# PCIE-to-USB3.net
KiCad netlist of a schematic drawn in Altium Designer
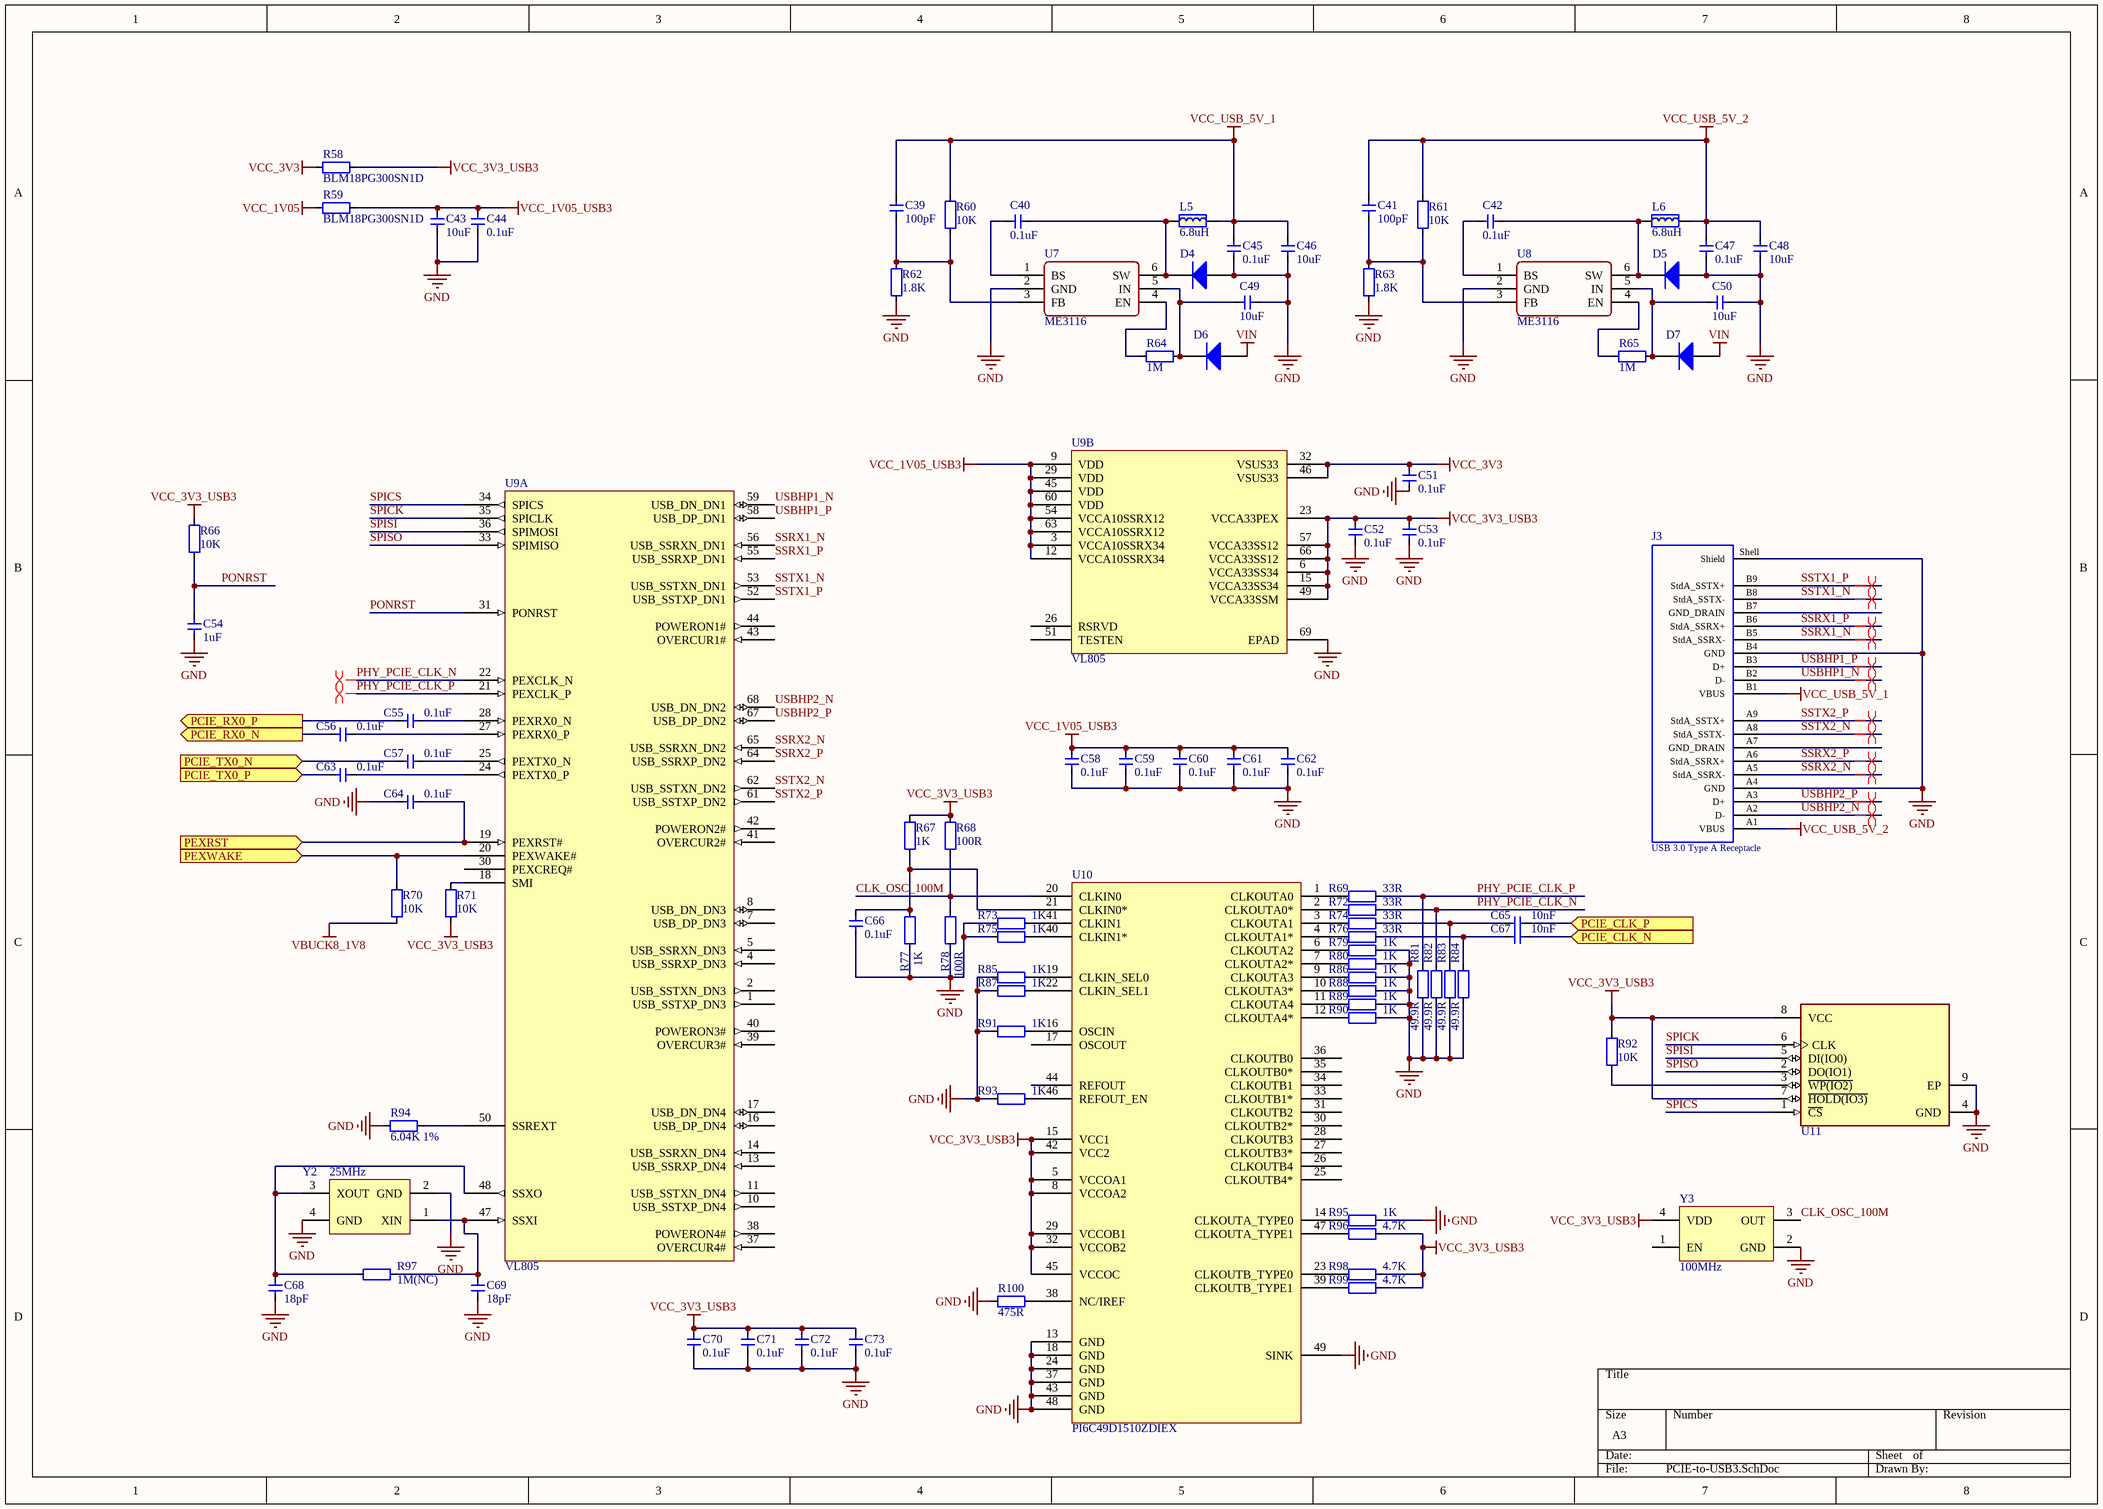
[diagram p0: PCIE-to-USB3.SchDoc]

(export (version "E")
  (design (tool "Eeschema 10.0.6"))
  (components
    (comp (ref "C39")
      (value "100pF")
      (footprint "CAP_0402")
      (description "Capacitor")
      (libsource (lib "MyPcbLib") (part "电容-0402"))
    )
    (comp (ref "C40")
      (value "0.1uF")
      (footprint "CAP_0402")
      (description "Capacitor")
      (libsource (lib "MyPcbLib") (part "电容-0402"))
    )
    (comp (ref "C41")
      (value "100pF")
      (footprint "CAP_0402")
      (description "Capacitor")
      (libsource (lib "MyPcbLib") (part "电容-0402"))
    )
    (comp (ref "C42")
      (value "0.1uF")
      (footprint "CAP_0402")
      (description "Capacitor")
      (libsource (lib "MyPcbLib") (part "电容-0402"))
    )
    (comp (ref "C43")
      (value "10uF")
      (footprint "CAP_0402")
      (description "Capacitor")
      (libsource (lib "MyPcbLib") (part "电容-0402"))
    )
    (comp (ref "C44")
      (value "0.1uF")
      (footprint "CAP_0402")
      (description "Capacitor")
      (libsource (lib "MyPcbLib") (part "电容-0402"))
    )
    (comp (ref "C45")
      (value "0.1uF")
      (footprint "CAP_0402")
      (description "Capacitor")
      (libsource (lib "MyPcbLib") (part "电容-0402"))
    )
    (comp (ref "C46")
      (value "10uF")
      (footprint "CAP_0402")
      (description "Capacitor")
      (libsource (lib "MyPcbLib") (part "电容-0402"))
    )
    (comp (ref "C47")
      (value "0.1uF")
      (footprint "CAP_0402")
      (description "Capacitor")
      (libsource (lib "MyPcbLib") (part "电容-0402"))
    )
    (comp (ref "C48")
      (value "10uF")
      (footprint "CAP_0402")
      (description "Capacitor")
      (libsource (lib "MyPcbLib") (part "电容-0402"))
    )
    (comp (ref "C49")
      (value "10uF")
      (footprint "CAP_0402")
      (description "Capacitor")
      (libsource (lib "MyPcbLib") (part "电容-0402"))
    )
    (comp (ref "C50")
      (value "10uF")
      (footprint "CAP_0402")
      (description "Capacitor")
      (libsource (lib "MyPcbLib") (part "电容-0402"))
    )
    (comp (ref "C51")
      (value "0.1uF")
      (footprint "CAP_0402")
      (description "Capacitor")
      (libsource (lib "MyPcbLib") (part "电容-0402"))
    )
    (comp (ref "C52")
      (value "0.1uF")
      (footprint "CAP_0402")
      (description "Capacitor")
      (libsource (lib "MyPcbLib") (part "电容-0402"))
    )
    (comp (ref "C53")
      (value "0.1uF")
      (footprint "CAP_0402")
      (description "Capacitor")
      (libsource (lib "MyPcbLib") (part "电容-0402"))
    )
    (comp (ref "C54")
      (value "1uF")
      (footprint "CAP_0402")
      (description "Capacitor")
      (libsource (lib "MyPcbLib") (part "电容-0402"))
    )
    (comp (ref "C55")
      (value "0.1uF")
      (footprint "CAP_0402")
      (description "Capacitor")
      (libsource (lib "MyPcbLib") (part "电容-0402"))
    )
    (comp (ref "C56")
      (value "0.1uF")
      (footprint "CAP_0402")
      (description "Capacitor")
      (libsource (lib "MyPcbLib") (part "电容-0402"))
    )
    (comp (ref "C57")
      (value "0.1uF")
      (footprint "CAP_0402")
      (description "Capacitor")
      (libsource (lib "MyPcbLib") (part "电容-0402"))
    )
    (comp (ref "C58")
      (value "0.1uF")
      (footprint "CAP_0402")
      (description "Capacitor")
      (libsource (lib "MyPcbLib") (part "电容-0402"))
    )
    (comp (ref "C59")
      (value "0.1uF")
      (footprint "CAP_0402")
      (description "Capacitor")
      (libsource (lib "MyPcbLib") (part "电容-0402"))
    )
    (comp (ref "C60")
      (value "0.1uF")
      (footprint "CAP_0402")
      (description "Capacitor")
      (libsource (lib "MyPcbLib") (part "电容-0402"))
    )
    (comp (ref "C61")
      (value "0.1uF")
      (footprint "CAP_0402")
      (description "Capacitor")
      (libsource (lib "MyPcbLib") (part "电容-0402"))
    )
    (comp (ref "C62")
      (value "0.1uF")
      (footprint "CAP_0402")
      (description "Capacitor")
      (libsource (lib "MyPcbLib") (part "电容-0402"))
    )
    (comp (ref "C63")
      (value "0.1uF")
      (footprint "CAP_0402")
      (description "Capacitor")
      (libsource (lib "MyPcbLib") (part "电容-0402"))
    )
    (comp (ref "C64")
      (value "0.1uF")
      (footprint "CAP_0402")
      (description "Capacitor")
      (libsource (lib "MyPcbLib") (part "电容-0402"))
    )
    (comp (ref "C65")
      (value "10nF")
      (footprint "CAP_0402")
      (description "Capacitor")
      (libsource (lib "MyPcbLib") (part "电容-0402"))
    )
    (comp (ref "C66")
      (value "0.1uF")
      (footprint "CAP_0402")
      (description "Capacitor")
      (libsource (lib "MyPcbLib") (part "电容-0402"))
    )
    (comp (ref "C67")
      (value "10nF")
      (footprint "CAP_0402")
      (description "Capacitor")
      (libsource (lib "MyPcbLib") (part "电容-0402"))
    )
    (comp (ref "C68")
      (value "18pF")
      (footprint "CAP_0402")
      (description "Capacitor")
      (libsource (lib "MyPcbLib") (part "电容-0402"))
    )
    (comp (ref "C69")
      (value "18pF")
      (footprint "CAP_0402")
      (description "Capacitor")
      (libsource (lib "MyPcbLib") (part "电容-0402"))
    )
    (comp (ref "C70")
      (value "0.1uF")
      (footprint "CAP_0402")
      (description "Capacitor")
      (libsource (lib "MyPcbLib") (part "电容-0402"))
    )
    (comp (ref "C71")
      (value "0.1uF")
      (footprint "CAP_0402")
      (description "Capacitor")
      (libsource (lib "MyPcbLib") (part "电容-0402"))
    )
    (comp (ref "C72")
      (value "0.1uF")
      (footprint "CAP_0402")
      (description "Capacitor")
      (libsource (lib "MyPcbLib") (part "电容-0402"))
    )
    (comp (ref "C73")
      (value "0.1uF")
      (footprint "CAP_0402")
      (description "Capacitor")
      (libsource (lib "MyPcbLib") (part "电容-0402"))
    )
    (comp (ref "D4")
      (value "二极管-5B5817WS")
      (footprint "SOD-323")
      (description "40V")
      (libsource (lib "MyPcbLib") (part "二极管-5B5817WS"))
    )
    (comp (ref "D5")
      (value "二极管-5B5817WS")
      (footprint "SOD-323")
      (description "40V")
      (libsource (lib "MyPcbLib") (part "二极管-5B5817WS"))
    )
    (comp (ref "D6")
      (value "二极管-5B5817WS")
      (footprint "SOD-323")
      (description "40V")
      (libsource (lib "MyPcbLib") (part "二极管-5B5817WS"))
    )
    (comp (ref "D7")
      (value "二极管-5B5817WS")
      (footprint "SOD-323")
      (description "40V")
      (libsource (lib "MyPcbLib") (part "二极管-5B5817WS"))
    )
    (comp (ref "J3")
      (value "USB 3.0 Type A Receptacle")
      (footprint "692141030100")
      (description "USB 3.0 Type A, Receptacle, Horizontal, THR, Dual Stacked")
      (fields
        (field (name "MANUFACTURER") "Wurth Elektronik")
        (field (name "MANUFACTURER PART NUMBER") "692141030100")
      )
      (libsource (lib "o80400v243+Altium_WR-USB+(rev20c)") (part "692141030100"))
    )
    (comp (ref "L5") (value "6.8uH") (footprint "IND-201612") (libsource (lib "MyPcbLib") (part "电感-201612")))
    (comp (ref "L6") (value "6.8uH") (footprint "IND-201612") (libsource (lib "MyPcbLib") (part "电感-201612")))
    (comp (ref "R58")
      (value "BLM18PG300SN1D")
      (footprint "0603-RES")
      (description "Resistor")
      (libsource (lib "MyPcbLib") (part "电阻-0603"))
    )
    (comp (ref "R59")
      (value "BLM18PG300SN1D")
      (footprint "0603-RES")
      (description "Resistor")
      (libsource (lib "MyPcbLib") (part "电阻-0603"))
    )
    (comp (ref "R60")
      (value "10K")
      (footprint "RES_0402")
      (description "Resistor")
      (libsource (lib "MyPcbLib") (part "电阻-0402"))
    )
    (comp (ref "R61")
      (value "10K")
      (footprint "RES_0402")
      (description "Resistor")
      (libsource (lib "MyPcbLib") (part "电阻-0402"))
    )
    (comp (ref "R62")
      (value "1.8K")
      (footprint "RES_0402")
      (description "Resistor")
      (libsource (lib "MyPcbLib") (part "电阻-0402"))
    )
    (comp (ref "R63")
      (value "1.8K")
      (footprint "RES_0402")
      (description "Resistor")
      (libsource (lib "MyPcbLib") (part "电阻-0402"))
    )
    (comp (ref "R64")
      (value "1M")
      (footprint "RES_0402")
      (description "Resistor")
      (libsource (lib "") (part "电阻-0402_1"))
    )
    (comp (ref "R65")
      (value "1M")
      (footprint "RES_0402")
      (description "Resistor")
      (libsource (lib "") (part "电阻-0402_1"))
    )
    (comp (ref "R66")
      (value "10K")
      (footprint "RES_0402")
      (description "Resistor")
      (libsource (lib "MyPcbLib") (part "电阻-0402"))
    )
    (comp (ref "R67")
      (value "1K")
      (footprint "RES_0402")
      (description "Resistor")
      (libsource (lib "MyPcbLib") (part "电阻-0402"))
    )
    (comp (ref "R68")
      (value "100R")
      (footprint "RES_0402")
      (description "Resistor")
      (libsource (lib "MyPcbLib") (part "电阻-0402"))
    )
    (comp (ref "R69")
      (value "33R")
      (footprint "RES_0402")
      (description "Resistor")
      (libsource (lib "") (part "电阻-0402_1"))
    )
    (comp (ref "R70")
      (value "10K")
      (footprint "RES_0402")
      (description "Resistor")
      (libsource (lib "MyPcbLib") (part "电阻-0402"))
    )
    (comp (ref "R71")
      (value "10K")
      (footprint "RES_0402")
      (description "Resistor")
      (libsource (lib "MyPcbLib") (part "电阻-0402"))
    )
    (comp (ref "R72")
      (value "33R")
      (footprint "RES_0402")
      (description "Resistor")
      (libsource (lib "") (part "电阻-0402_1"))
    )
    (comp (ref "R73")
      (value "1K")
      (footprint "RES_0402")
      (description "Resistor")
      (libsource (lib "") (part "电阻-0402_1"))
    )
    (comp (ref "R74")
      (value "33R")
      (footprint "RES_0402")
      (description "Resistor")
      (libsource (lib "") (part "电阻-0402_1"))
    )
    (comp (ref "R75")
      (value "1K")
      (footprint "RES_0402")
      (description "Resistor")
      (libsource (lib "") (part "电阻-0402_1"))
    )
    (comp (ref "R76")
      (value "33R")
      (footprint "RES_0402")
      (description "Resistor")
      (libsource (lib "") (part "电阻-0402_1"))
    )
    (comp (ref "R77")
      (value "1K")
      (footprint "RES_0402")
      (description "Resistor")
      (libsource (lib "MyPcbLib") (part "电阻-0402"))
    )
    (comp (ref "R78")
      (value "100R")
      (footprint "RES_0402")
      (description "Resistor")
      (libsource (lib "MyPcbLib") (part "电阻-0402"))
    )
    (comp (ref "R79")
      (value "1K")
      (footprint "RES_0402")
      (description "Resistor")
      (libsource (lib "") (part "电阻-0402_1"))
    )
    (comp (ref "R80")
      (value "1K")
      (footprint "RES_0402")
      (description "Resistor")
      (libsource (lib "") (part "电阻-0402_1"))
    )
    (comp (ref "R81")
      (value "49.9R")
      (footprint "RES_0402")
      (description "Resistor")
      (libsource (lib "") (part "电阻-0402_2"))
    )
    (comp (ref "R82")
      (value "49.9R")
      (footprint "RES_0402")
      (description "Resistor")
      (libsource (lib "") (part "电阻-0402_2"))
    )
    (comp (ref "R83")
      (value "49.9R")
      (footprint "RES_0402")
      (description "Resistor")
      (libsource (lib "") (part "电阻-0402_2"))
    )
    (comp (ref "R84")
      (value "49.9R")
      (footprint "RES_0402")
      (description "Resistor")
      (libsource (lib "") (part "电阻-0402_2"))
    )
    (comp (ref "R85")
      (value "1K")
      (footprint "RES_0402")
      (description "Resistor")
      (libsource (lib "") (part "电阻-0402_1"))
    )
    (comp (ref "R86")
      (value "1K")
      (footprint "RES_0402")
      (description "Resistor")
      (libsource (lib "") (part "电阻-0402_1"))
    )
    (comp (ref "R87")
      (value "1K")
      (footprint "RES_0402")
      (description "Resistor")
      (libsource (lib "") (part "电阻-0402_1"))
    )
    (comp (ref "R88")
      (value "1K")
      (footprint "RES_0402")
      (description "Resistor")
      (libsource (lib "") (part "电阻-0402_1"))
    )
    (comp (ref "R89")
      (value "1K")
      (footprint "RES_0402")
      (description "Resistor")
      (libsource (lib "") (part "电阻-0402_1"))
    )
    (comp (ref "R90")
      (value "1K")
      (footprint "RES_0402")
      (description "Resistor")
      (libsource (lib "") (part "电阻-0402_1"))
    )
    (comp (ref "R91")
      (value "1K")
      (footprint "RES_0402")
      (description "Resistor")
      (libsource (lib "") (part "电阻-0402_1"))
    )
    (comp (ref "R92")
      (value "10K")
      (footprint "RES_0402")
      (description "Resistor")
      (libsource (lib "") (part "电阻-0402_2"))
    )
    (comp (ref "R93")
      (value "1K")
      (footprint "RES_0402")
      (description "Resistor")
      (libsource (lib "") (part "电阻-0402_1"))
    )
    (comp (ref "R94")
      (value "6.04K 1%")
      (footprint "RES_0402")
      (description "Resistor")
      (libsource (lib "") (part "电阻-0402_3"))
    )
    (comp (ref "R95")
      (value "1K")
      (footprint "RES_0402")
      (description "Resistor")
      (libsource (lib "") (part "电阻-0402_1"))
    )
    (comp (ref "R96")
      (value "4.7K")
      (footprint "RES_0402")
      (description "Resistor")
      (libsource (lib "") (part "电阻-0402_1"))
    )
    (comp (ref "R97")
      (value "1M(NC)")
      (footprint "RES_0402")
      (description "Resistor")
      (libsource (lib "") (part "电阻-0402_1"))
    )
    (comp (ref "R98")
      (value "4.7K")
      (footprint "RES_0402")
      (description "Resistor")
      (libsource (lib "") (part "电阻-0402_1"))
    )
    (comp (ref "R99")
      (value "4.7K")
      (footprint "RES_0402")
      (description "Resistor")
      (libsource (lib "") (part "电阻-0402_1"))
    )
    (comp (ref "R100")
      (value "475R")
      (footprint "RES_0402")
      (description "Resistor")
      (libsource (lib "") (part "电阻-0402_3"))
    )
    (comp (ref "U7")
      (value "ME3116")
      (footprint "SOT23-6")
      (description "DC-DC")
      (libsource (lib "MyPcbLib") (part "ME3116"))
    )
    (comp (ref "U8")
      (value "ME3116")
      (footprint "SOT23-6")
      (description "DC-DC")
      (libsource (lib "MyPcbLib") (part "ME3116"))
    )
    (comp (ref "U9")
      (value "VL805")
      (footprint "QFN-68-0.4MM")
      (description "PCIE to USB3.0")
      (libsource (lib "mLib") (part "VL805"))
    )
    (comp (ref "U10")
      (value "PI6C49D1510ZDIEX")
      (footprint "QFN-48_7X7")
      (libsource (lib "MyPcbLib") (part "PI6C49D1510ZDIEX"))
    )
    (comp (ref "U11")
      (value "W25Q80DVUXIE_TR")
      (footprint "SPI-FLASH-USON")
      (libsource (lib "MyPcbLib") (part "W25Q80DVUXIE_TR"))
    )
    (comp (ref "Y2")
      (value "25MHz")
      (footprint "晶振2520")
      (description "2520无源")
      (fields (field (name "MF") "ECS International") (field (name "MP") "ECS-3225S30-240-EN-TR"))
      (libsource (lib "MyPcbLib") (part "晶振-4Pin-无源"))
    )
    (comp (ref "Y3")
      (value "100MHz")
      (footprint "晶振2520")
      (description "2520")
      (libsource (lib "MyPcbLib") (part "晶振-4Pin-有源"))
    )
  )
  (nets
    (net (code "1") (name "/CLK_OSC_100M") (class "Default")
      (node (ref "R68") (pin "1") (pinfunction "1_1") (pintype "passive"))
      (node (ref "R78") (pin "2") (pinfunction "2_2") (pintype "passive"))
      (node (ref "U10") (pin "20") (pinfunction "CLKIN0_20") (pintype "power_in"))
      (node (ref "Y3") (pin "3") (pinfunction "OUT_3") (pintype "passive"))
    )
    (net (code "2") (name "/PCIE_CLK_N") (class "Default")
      (node (ref "C67") (pin "1") (pinfunction "1_1") (pintype "passive"))
    )
    (net (code "3") (name "/PCIE_CLK_P") (class "Default")
      (node (ref "C65") (pin "1") (pinfunction "1_1") (pintype "passive"))
    )
    (net (code "4") (name "/PCIE_RX0_N") (class "Default")
      (node (ref "C56") (pin "1") (pinfunction "1_1") (pintype "passive"))
    )
    (net (code "5") (name "/PCIE_RX0_P") (class "Default")
      (node (ref "C55") (pin "1") (pinfunction "1_1") (pintype "passive"))
    )
    (net (code "6") (name "/PCIE_TX0_N") (class "Default")
      (node (ref "C57") (pin "1") (pinfunction "1_1") (pintype "passive"))
    )
    (net (code "7") (name "/PCIE_TX0_P") (class "Default")
      (node (ref "C63") (pin "1") (pinfunction "1_1") (pintype "passive"))
    )
    (net (code "8") (name "/PEXRST") (class "Default")
      (node (ref "C64") (pin "2") (pinfunction "2_2") (pintype "passive"))
      (node (ref "U9") (pin "19") (pinfunction "PEXRST#_19") (pintype "input"))
    )
    (net (code "9") (name "/PEXWAKE") (class "Default")
      (node (ref "R70") (pin "2") (pinfunction "2_2") (pintype "passive"))
      (node (ref "U9") (pin "20") (pinfunction "PEXWAKE#_20") (pintype "passive"))
    )
    (net (code "10") (name "/PHY_PCIE_CLK_N") (class "Default")
      (node (ref "R72") (pin "1") (pinfunction "1_1") (pintype "passive"))
      (node (ref "R82") (pin "1") (pinfunction "1_1") (pintype "passive"))
      (node (ref "U9") (pin "22") (pinfunction "PEXCLK_N_22") (pintype "input"))
    )
    (net (code "11") (name "/PHY_PCIE_CLK_P") (class "Default")
      (node (ref "R69") (pin "1") (pinfunction "1_1") (pintype "passive"))
      (node (ref "R81") (pin "1") (pinfunction "1_1") (pintype "passive"))
      (node (ref "U9") (pin "21") (pinfunction "PEXCLK_P_21") (pintype "input"))
    )
    (net (code "12") (name "/PONRST") (class "Default")
      (node (ref "C54") (pin "1") (pinfunction "1_1") (pintype "passive"))
      (node (ref "R66") (pin "1") (pinfunction "1_1") (pintype "passive"))
      (node (ref "U9") (pin "31") (pinfunction "PONRST_31") (pintype "input"))
    )
    (net (code "13") (name "/SPICK") (class "Default")
      (node (ref "U11") (pin "6") (pinfunction "CLK_6") (pintype "input"))
      (node (ref "U9") (pin "35") (pinfunction "SPICLK_35") (pintype "output"))
    )
    (net (code "14") (name "/SPICS") (class "Default")
      (node (ref "U11") (pin "1") (pinfunction "~{CS}_1") (pintype "input"))
      (node (ref "U9") (pin "34") (pinfunction "SPICS_34") (pintype "output"))
    )
    (net (code "15") (name "/SPISI") (class "Default")
      (node (ref "U11") (pin "5") (pinfunction "DI(IO0)_5") (pintype "bidirectional"))
      (node (ref "U9") (pin "36") (pinfunction "SPIMOSI_36") (pintype "output"))
    )
    (net (code "16") (name "/SPISO") (class "Default")
      (node (ref "U11") (pin "2") (pinfunction "DO(IO1)_2") (pintype "bidirectional"))
      (node (ref "U9") (pin "33") (pinfunction "SPIMISO_33") (pintype "input"))
    )
    (net (code "17") (name "/SSRX1_N") (class "Default")
      (node (ref "J3") (pin "B5") (pinfunction "StdA_SSRX-_B5") (pintype "passive"))
      (node (ref "U9") (pin "56") (pinfunction "USB_SSRXN_DN1_56") (pintype "input"))
    )
    (net (code "18") (name "/SSRX1_P") (class "Default")
      (node (ref "J3") (pin "B6") (pinfunction "StdA_SSRX+_B6") (pintype "passive"))
      (node (ref "U9") (pin "55") (pinfunction "USB_SSRXP_DN1_55") (pintype "input"))
    )
    (net (code "19") (name "/SSRX2_N") (class "Default")
      (node (ref "J3") (pin "A5") (pinfunction "StdA_SSRX-_A5") (pintype "passive"))
      (node (ref "U9") (pin "65") (pinfunction "USB_SSRXN_DN2_65") (pintype "input"))
    )
    (net (code "20") (name "/SSRX2_P") (class "Default")
      (node (ref "J3") (pin "A6") (pinfunction "StdA_SSRX+_A6") (pintype "passive"))
      (node (ref "U9") (pin "64") (pinfunction "USB_SSRXP_DN2_64") (pintype "input"))
    )
    (net (code "21") (name "/SSTX1_N") (class "Default")
      (node (ref "J3") (pin "B8") (pinfunction "StdA_SSTX-_B8") (pintype "passive"))
      (node (ref "U9") (pin "53") (pinfunction "USB_SSTXN_DN1_53") (pintype "output"))
    )
    (net (code "22") (name "/SSTX1_P") (class "Default")
      (node (ref "J3") (pin "B9") (pinfunction "StdA_SSTX+_B9") (pintype "passive"))
      (node (ref "U9") (pin "52") (pinfunction "USB_SSTXP_DN1_52") (pintype "output"))
    )
    (net (code "23") (name "/SSTX2_N") (class "Default")
      (node (ref "J3") (pin "A8") (pinfunction "StdA_SSTX-_A8") (pintype "passive"))
      (node (ref "U9") (pin "62") (pinfunction "USB_SSTXN_DN2_62") (pintype "output"))
    )
    (net (code "24") (name "/SSTX2_P") (class "Default")
      (node (ref "J3") (pin "A9") (pinfunction "StdA_SSTX+_A9") (pintype "passive"))
      (node (ref "U9") (pin "61") (pinfunction "USB_SSTXP_DN2_61") (pintype "output"))
    )
    (net (code "25") (name "/USBHP1_N") (class "Default")
      (node (ref "J3") (pin "B2") (pinfunction "D-_B2") (pintype "passive"))
      (node (ref "U9") (pin "59") (pinfunction "USB_DN_DN1_59") (pintype "bidirectional"))
    )
    (net (code "26") (name "/USBHP1_P") (class "Default")
      (node (ref "J3") (pin "B3") (pinfunction "D+_B3") (pintype "passive"))
      (node (ref "U9") (pin "58") (pinfunction "USB_DP_DN1_58") (pintype "bidirectional"))
    )
    (net (code "27") (name "/USBHP2_N") (class "Default")
      (node (ref "J3") (pin "A2") (pinfunction "D-_A2") (pintype "passive"))
      (node (ref "U9") (pin "68") (pinfunction "USB_DN_DN2_68") (pintype "bidirectional"))
    )
    (net (code "28") (name "/USBHP2_P") (class "Default")
      (node (ref "J3") (pin "A3") (pinfunction "D+_A3") (pintype "passive"))
      (node (ref "U9") (pin "67") (pinfunction "USB_DP_DN2_67") (pintype "bidirectional"))
    )
    (net (code "29") (name "GND") (class "Default")
      (node (ref "C43") (pin "2") (pinfunction "2_2") (pintype "passive"))
      (node (ref "C44") (pin "2") (pinfunction "2_2") (pintype "passive"))
      (node (ref "C45") (pin "1") (pinfunction "1_1") (pintype "passive"))
      (node (ref "C46") (pin "1") (pinfunction "1_1") (pintype "passive"))
      (node (ref "C47") (pin "1") (pinfunction "1_1") (pintype "passive"))
      (node (ref "C48") (pin "1") (pinfunction "1_1") (pintype "passive"))
      (node (ref "C49") (pin "1") (pinfunction "1_1") (pintype "passive"))
      (node (ref "C50") (pin "1") (pinfunction "1_1") (pintype "passive"))
      (node (ref "C51") (pin "1") (pinfunction "1_1") (pintype "passive"))
      (node (ref "C52") (pin "1") (pinfunction "1_1") (pintype "passive"))
      (node (ref "C53") (pin "1") (pinfunction "1_1") (pintype "passive"))
      (node (ref "C54") (pin "2") (pinfunction "2_2") (pintype "passive"))
      (node (ref "C58") (pin "1") (pinfunction "1_1") (pintype "passive"))
      (node (ref "C59") (pin "1") (pinfunction "1_1") (pintype "passive"))
      (node (ref "C60") (pin "1") (pinfunction "1_1") (pintype "passive"))
      (node (ref "C61") (pin "1") (pinfunction "1_1") (pintype "passive"))
      (node (ref "C62") (pin "1") (pinfunction "1_1") (pintype "passive"))
      (node (ref "C64") (pin "1") (pinfunction "1_1") (pintype "passive"))
      (node (ref "C66") (pin "1") (pinfunction "1_1") (pintype "passive"))
      (node (ref "C68") (pin "1") (pinfunction "1_1") (pintype "passive"))
      (node (ref "C69") (pin "1") (pinfunction "1_1") (pintype "passive"))
      (node (ref "C70") (pin "1") (pinfunction "1_1") (pintype "passive"))
      (node (ref "C71") (pin "1") (pinfunction "1_1") (pintype "passive"))
      (node (ref "C72") (pin "1") (pinfunction "1_1") (pintype "passive"))
      (node (ref "C73") (pin "1") (pinfunction "1_1") (pintype "passive"))
      (node (ref "D4") (pin "1") (pinfunction "A_1") (pintype "passive"))
      (node (ref "D5") (pin "1") (pinfunction "A_1") (pintype "passive"))
      (node (ref "J3") (pin "A4") (pinfunction "GND_A4") (pintype "passive"))
      (node (ref "J3") (pin "B4") (pinfunction "GND_B4") (pintype "passive"))
      (node (ref "J3") (pin "Shell") (pinfunction "Shield_Shell") (pintype "passive"))
      (node (ref "R100") (pin "1") (pinfunction "1_1") (pintype "passive"))
      (node (ref "R62") (pin "1") (pinfunction "1_1") (pintype "passive"))
      (node (ref "R63") (pin "1") (pinfunction "1_1") (pintype "passive"))
      (node (ref "R73") (pin "2") (pinfunction "2_2") (pintype "passive"))
      (node (ref "R75") (pin "2") (pinfunction "2_2") (pintype "passive"))
      (node (ref "R77") (pin "1") (pinfunction "1_1") (pintype "passive"))
      (node (ref "R78") (pin "1") (pinfunction "1_1") (pintype "passive"))
      (node (ref "R79") (pin "1") (pinfunction "1_1") (pintype "passive"))
      (node (ref "R80") (pin "1") (pinfunction "1_1") (pintype "passive"))
      (node (ref "R81") (pin "2") (pinfunction "2_2") (pintype "passive"))
      (node (ref "R82") (pin "2") (pinfunction "2_2") (pintype "passive"))
      (node (ref "R83") (pin "2") (pinfunction "2_2") (pintype "passive"))
      (node (ref "R84") (pin "2") (pinfunction "2_2") (pintype "passive"))
      (node (ref "R85") (pin "2") (pinfunction "2_2") (pintype "passive"))
      (node (ref "R86") (pin "1") (pinfunction "1_1") (pintype "passive"))
      (node (ref "R87") (pin "2") (pinfunction "2_2") (pintype "passive"))
      (node (ref "R88") (pin "1") (pinfunction "1_1") (pintype "passive"))
      (node (ref "R89") (pin "1") (pinfunction "1_1") (pintype "passive"))
      (node (ref "R90") (pin "1") (pinfunction "1_1") (pintype "passive"))
      (node (ref "R91") (pin "2") (pinfunction "2_2") (pintype "passive"))
      (node (ref "R93") (pin "2") (pinfunction "2_2") (pintype "passive"))
      (node (ref "R94") (pin "1") (pinfunction "1_1") (pintype "passive"))
      (node (ref "R95") (pin "1") (pinfunction "1_1") (pintype "passive"))
      (node (ref "U10") (pin "13") (pinfunction "GND_13") (pintype "power_in"))
      (node (ref "U10") (pin "18") (pinfunction "GND_18") (pintype "power_in"))
      (node (ref "U10") (pin "24") (pinfunction "GND_24") (pintype "power_in"))
      (node (ref "U10") (pin "37") (pinfunction "GND_37") (pintype "power_in"))
      (node (ref "U10") (pin "43") (pinfunction "GND_43") (pintype "power_in"))
      (node (ref "U10") (pin "48") (pinfunction "GND_48") (pintype "power_in"))
      (node (ref "U10") (pin "49") (pinfunction "SINK_49") (pintype "power_in"))
      (node (ref "U11") (pin "4") (pinfunction "GND_4") (pintype "power_in"))
      (node (ref "U11") (pin "9") (pinfunction "EP_9") (pintype "passive"))
      (node (ref "U7") (pin "2") (pinfunction "GND_2") (pintype "passive"))
      (node (ref "U8") (pin "2") (pinfunction "GND_2") (pintype "passive"))
      (node (ref "U9") (pin "69") (pinfunction "EPAD_69") (pintype "power_in"))
      (node (ref "Y2") (pin "2") (pinfunction "GND_2") (pintype "passive"))
      (node (ref "Y2") (pin "4") (pinfunction "GND_4") (pintype "passive"))
      (node (ref "Y3") (pin "2") (pinfunction "GND_2") (pintype "passive"))
    )
    (net (code "30") (name "Net-(C65-Pad2)") (class "Default")
      (node (ref "C65") (pin "2") (pinfunction "2_2") (pintype "passive"))
      (node (ref "R74") (pin "1") (pinfunction "1_1") (pintype "passive"))
      (node (ref "R83") (pin "1") (pinfunction "1_1") (pintype "passive"))
    )
    (net (code "31") (name "Net-(C67-Pad2)") (class "Default")
      (node (ref "C67") (pin "2") (pinfunction "2_2") (pintype "passive"))
      (node (ref "R76") (pin "1") (pinfunction "1_1") (pintype "passive"))
      (node (ref "R84") (pin "1") (pinfunction "1_1") (pintype "passive"))
    )
    (net (code "32") (name "Net-(D4-K)") (class "Default")
      (node (ref "C40") (pin "1") (pinfunction "1_1") (pintype "passive"))
      (node (ref "D4") (pin "2") (pinfunction "K_2") (pintype "passive"))
      (node (ref "L5") (pin "1") (pintype "passive"))
      (node (ref "U7") (pin "6") (pinfunction "SW_6") (pintype "passive"))
    )
    (net (code "33") (name "Net-(D5-K)") (class "Default")
      (node (ref "C42") (pin "1") (pinfunction "1_1") (pintype "passive"))
      (node (ref "D5") (pin "2") (pinfunction "K_2") (pintype "passive"))
      (node (ref "L6") (pin "1") (pintype "passive"))
      (node (ref "U8") (pin "6") (pinfunction "SW_6") (pintype "passive"))
    )
    (net (code "34") (name "Net-(D6-K)") (class "Default")
      (node (ref "C49") (pin "2") (pinfunction "2_2") (pintype "passive"))
      (node (ref "D6") (pin "2") (pinfunction "K_2") (pintype "passive"))
      (node (ref "R64") (pin "1") (pinfunction "1_1") (pintype "passive"))
      (node (ref "U7") (pin "5") (pinfunction "IN_5") (pintype "passive"))
    )
    (net (code "35") (name "Net-(D7-K)") (class "Default")
      (node (ref "C50") (pin "2") (pinfunction "2_2") (pintype "passive"))
      (node (ref "D7") (pin "2") (pinfunction "K_2") (pintype "passive"))
      (node (ref "R65") (pin "1") (pinfunction "1_1") (pintype "passive"))
      (node (ref "U8") (pin "5") (pinfunction "IN_5") (pintype "passive"))
    )
    (net (code "36") (name "Net-(U7-BS)") (class "Default")
      (node (ref "C40") (pin "2") (pinfunction "2_2") (pintype "passive"))
      (node (ref "U7") (pin "1") (pinfunction "BS_1") (pintype "passive"))
    )
    (net (code "37") (name "Net-(U7-EN)") (class "Default")
      (node (ref "R64") (pin "2") (pinfunction "2_2") (pintype "passive"))
      (node (ref "U7") (pin "4") (pinfunction "EN_4") (pintype "passive"))
    )
    (net (code "38") (name "Net-(U7-FB)") (class "Default")
      (node (ref "C39") (pin "2") (pinfunction "2_2") (pintype "passive"))
      (node (ref "R60") (pin "1") (pinfunction "1_1") (pintype "passive"))
      (node (ref "R62") (pin "2") (pinfunction "2_2") (pintype "passive"))
      (node (ref "U7") (pin "3") (pinfunction "FB_3") (pintype "passive"))
    )
    (net (code "39") (name "Net-(U8-BS)") (class "Default")
      (node (ref "C42") (pin "2") (pinfunction "2_2") (pintype "passive"))
      (node (ref "U8") (pin "1") (pinfunction "BS_1") (pintype "passive"))
    )
    (net (code "40") (name "Net-(U8-EN)") (class "Default")
      (node (ref "R65") (pin "2") (pinfunction "2_2") (pintype "passive"))
      (node (ref "U8") (pin "4") (pinfunction "EN_4") (pintype "passive"))
    )
    (net (code "41") (name "Net-(U8-FB)") (class "Default")
      (node (ref "C41") (pin "2") (pinfunction "2_2") (pintype "passive"))
      (node (ref "R61") (pin "1") (pinfunction "1_1") (pintype "passive"))
      (node (ref "R63") (pin "2") (pinfunction "2_2") (pintype "passive"))
      (node (ref "U8") (pin "3") (pinfunction "FB_3") (pintype "passive"))
    )
    (net (code "42") (name "Net-(U9A-PEXRX0_N)") (class "Default")
      (node (ref "C55") (pin "2") (pinfunction "2_2") (pintype "passive"))
      (node (ref "U9") (pin "28") (pinfunction "PEXRX0_N_28") (pintype "input"))
    )
    (net (code "43") (name "Net-(U9A-PEXRX0_P)") (class "Default")
      (node (ref "C56") (pin "2") (pinfunction "2_2") (pintype "passive"))
      (node (ref "U9") (pin "27") (pinfunction "PEXRX0_P_27") (pintype "input"))
    )
    (net (code "44") (name "Net-(U9A-PEXTX0_N)") (class "Default")
      (node (ref "C57") (pin "2") (pinfunction "2_2") (pintype "passive"))
      (node (ref "U9") (pin "25") (pinfunction "PEXTX0_N_25") (pintype "output"))
    )
    (net (code "45") (name "Net-(U9A-PEXTX0_P)") (class "Default")
      (node (ref "C63") (pin "2") (pinfunction "2_2") (pintype "passive"))
      (node (ref "U9") (pin "24") (pinfunction "PEXTX0_P_24") (pintype "output"))
    )
    (net (code "46") (name "Net-(U9A-SMI)") (class "Default")
      (node (ref "R71") (pin "2") (pinfunction "2_2") (pintype "passive"))
      (node (ref "U9") (pin "18") (pinfunction "SMI_18") (pintype "passive"))
    )
    (net (code "47") (name "Net-(U9A-SSREXT)") (class "Default")
      (node (ref "R94") (pin "2") (pinfunction "2_2") (pintype "passive"))
      (node (ref "U9") (pin "50") (pinfunction "SSREXT_50") (pintype "passive"))
    )
    (net (code "48") (name "Net-(U9A-SSXI)") (class "Default")
      (node (ref "C69") (pin "2") (pinfunction "2_2") (pintype "passive"))
      (node (ref "R97") (pin "1") (pinfunction "1_1") (pintype "passive"))
      (node (ref "U9") (pin "47") (pinfunction "SSXI_47") (pintype "input"))
      (node (ref "Y2") (pin "1") (pinfunction "XIN_1") (pintype "passive"))
    )
    (net (code "49") (name "Net-(U9A-SSXO)") (class "Default")
      (node (ref "C68") (pin "2") (pinfunction "2_2") (pintype "passive"))
      (node (ref "R97") (pin "2") (pinfunction "2_2") (pintype "passive"))
      (node (ref "U9") (pin "48") (pinfunction "SSXO_48") (pintype "output"))
      (node (ref "Y2") (pin "3") (pinfunction "XOUT_3") (pintype "passive"))
    )
    (net (code "50") (name "Net-(U10-CLKIN0*)") (class "Default")
      (node (ref "C66") (pin "2") (pinfunction "2_2") (pintype "passive"))
      (node (ref "R67") (pin "1") (pinfunction "1_1") (pintype "passive"))
      (node (ref "R77") (pin "2") (pinfunction "2_2") (pintype "passive"))
      (node (ref "U10") (pin "21") (pinfunction "CLKIN0*_21") (pintype "power_in"))
    )
    (net (code "51") (name "Net-(U10-CLKIN1)") (class "Default")
      (node (ref "R73") (pin "1") (pinfunction "1_1") (pintype "passive"))
      (node (ref "U10") (pin "41") (pinfunction "CLKIN1_41") (pintype "power_in"))
    )
    (net (code "52") (name "Net-(U10-CLKIN1*)") (class "Default")
      (node (ref "R75") (pin "1") (pinfunction "1_1") (pintype "passive"))
      (node (ref "U10") (pin "40") (pinfunction "CLKIN1*_40") (pintype "power_in"))
    )
    (net (code "53") (name "Net-(U10-CLKIN_SEL0)") (class "Default")
      (node (ref "R85") (pin "1") (pinfunction "1_1") (pintype "passive"))
      (node (ref "U10") (pin "19") (pinfunction "CLKIN_SEL0_19") (pintype "power_in"))
    )
    (net (code "54") (name "Net-(U10-CLKIN_SEL1)") (class "Default")
      (node (ref "R87") (pin "1") (pinfunction "1_1") (pintype "passive"))
      (node (ref "U10") (pin "22") (pinfunction "CLKIN_SEL1_22") (pintype "power_in"))
    )
    (net (code "55") (name "Net-(U10-CLKOUTA0)") (class "Default")
      (node (ref "R69") (pin "2") (pinfunction "2_2") (pintype "passive"))
      (node (ref "U10") (pin "1") (pinfunction "CLKOUTA0_1") (pintype "power_in"))
    )
    (net (code "56") (name "Net-(U10-CLKOUTA0*)") (class "Default")
      (node (ref "R72") (pin "2") (pinfunction "2_2") (pintype "passive"))
      (node (ref "U10") (pin "2") (pinfunction "CLKOUTA0*_2") (pintype "power_in"))
    )
    (net (code "57") (name "Net-(U10-CLKOUTA1)") (class "Default")
      (node (ref "R74") (pin "2") (pinfunction "2_2") (pintype "passive"))
      (node (ref "U10") (pin "3") (pinfunction "CLKOUTA1_3") (pintype "power_in"))
    )
    (net (code "58") (name "Net-(U10-CLKOUTA1*)") (class "Default")
      (node (ref "R76") (pin "2") (pinfunction "2_2") (pintype "passive"))
      (node (ref "U10") (pin "4") (pinfunction "CLKOUTA1*_4") (pintype "power_in"))
    )
    (net (code "59") (name "Net-(U10-CLKOUTA2)") (class "Default")
      (node (ref "R79") (pin "2") (pinfunction "2_2") (pintype "passive"))
      (node (ref "U10") (pin "6") (pinfunction "CLKOUTA2_6") (pintype "power_in"))
    )
    (net (code "60") (name "Net-(U10-CLKOUTA2*)") (class "Default")
      (node (ref "R80") (pin "2") (pinfunction "2_2") (pintype "passive"))
      (node (ref "U10") (pin "7") (pinfunction "CLKOUTA2*_7") (pintype "power_in"))
    )
    (net (code "61") (name "Net-(U10-CLKOUTA3)") (class "Default")
      (node (ref "R86") (pin "2") (pinfunction "2_2") (pintype "passive"))
      (node (ref "U10") (pin "9") (pinfunction "CLKOUTA3_9") (pintype "power_in"))
    )
    (net (code "62") (name "Net-(U10-CLKOUTA3*)") (class "Default")
      (node (ref "R88") (pin "2") (pinfunction "2_2") (pintype "passive"))
      (node (ref "U10") (pin "10") (pinfunction "CLKOUTA3*_10") (pintype "power_in"))
    )
    (net (code "63") (name "Net-(U10-CLKOUTA4)") (class "Default")
      (node (ref "R89") (pin "2") (pinfunction "2_2") (pintype "passive"))
      (node (ref "U10") (pin "11") (pinfunction "CLKOUTA4_11") (pintype "power_in"))
    )
    (net (code "64") (name "Net-(U10-CLKOUTA4*)") (class "Default")
      (node (ref "R90") (pin "2") (pinfunction "2_2") (pintype "passive"))
      (node (ref "U10") (pin "12") (pinfunction "CLKOUTA4*_12") (pintype "power_in"))
    )
    (net (code "65") (name "Net-(U10-CLKOUTA_TYPE0)") (class "Default")
      (node (ref "R95") (pin "2") (pinfunction "2_2") (pintype "passive"))
      (node (ref "U10") (pin "14") (pinfunction "CLKOUTA_TYPE0_14") (pintype "power_in"))
    )
    (net (code "66") (name "Net-(U10-CLKOUTA_TYPE1)") (class "Default")
      (node (ref "R96") (pin "2") (pinfunction "2_2") (pintype "passive"))
      (node (ref "U10") (pin "47") (pinfunction "CLKOUTA_TYPE1_47") (pintype "power_in"))
    )
    (net (code "67") (name "Net-(U10-CLKOUTB_TYPE0)") (class "Default")
      (node (ref "R98") (pin "2") (pinfunction "2_2") (pintype "passive"))
      (node (ref "U10") (pin "23") (pinfunction "CLKOUTB_TYPE0_23") (pintype "power_in"))
    )
    (net (code "68") (name "Net-(U10-CLKOUTB_TYPE1)") (class "Default")
      (node (ref "R99") (pin "2") (pinfunction "2_2") (pintype "passive"))
      (node (ref "U10") (pin "39") (pinfunction "CLKOUTB_TYPE1_39") (pintype "power_in"))
    )
    (net (code "69") (name "Net-(U10-NC{slash}IREF)") (class "Default")
      (node (ref "R100") (pin "2") (pinfunction "2_2") (pintype "passive"))
      (node (ref "U10") (pin "38") (pinfunction "NC/IREF_38") (pintype "power_in"))
    )
    (net (code "70") (name "Net-(U10-OSCIN)") (class "Default")
      (node (ref "R91") (pin "1") (pinfunction "1_1") (pintype "passive"))
      (node (ref "U10") (pin "16") (pinfunction "OSCIN_16") (pintype "power_in"))
    )
    (net (code "71") (name "Net-(U10-REFOUT_EN)") (class "Default")
      (node (ref "R93") (pin "1") (pinfunction "1_1") (pintype "passive"))
      (node (ref "U10") (pin "46") (pinfunction "REFOUT_EN_46") (pintype "power_in"))
    )
    (net (code "72") (name "Net-(U11-~{WP(IO2)})") (class "Default")
      (node (ref "R92") (pin "2") (pinfunction "2_2") (pintype "passive"))
      (node (ref "U11") (pin "3") (pinfunction "~{WP(IO2)}_3") (pintype "bidirectional"))
    )
    (net (code "73") (name "VBUCK8_1V8") (class "Default")
      (node (ref "R70") (pin "1") (pinfunction "1_1") (pintype "passive"))
    )
    (net (code "74") (name "VCC_1V05") (class "Default")
      (node (ref "R59") (pin "1") (pinfunction "1_1") (pintype "passive"))
    )
    (net (code "75") (name "VCC_1V05_USB3") (class "Default")
      (node (ref "C43") (pin "1") (pinfunction "1_1") (pintype "passive"))
      (node (ref "C44") (pin "1") (pinfunction "1_1") (pintype "passive"))
      (node (ref "C58") (pin "2") (pinfunction "2_2") (pintype "passive"))
      (node (ref "C59") (pin "2") (pinfunction "2_2") (pintype "passive"))
      (node (ref "C60") (pin "2") (pinfunction "2_2") (pintype "passive"))
      (node (ref "C61") (pin "2") (pinfunction "2_2") (pintype "passive"))
      (node (ref "C62") (pin "2") (pinfunction "2_2") (pintype "passive"))
      (node (ref "R59") (pin "2") (pinfunction "2_2") (pintype "passive"))
      (node (ref "U9") (pin "12") (pinfunction "VCCA10SSRX34_12") (pintype "power_in"))
      (node (ref "U9") (pin "29") (pinfunction "VDD_29") (pintype "power_in"))
      (node (ref "U9") (pin "3") (pinfunction "VCCA10SSRX34_3") (pintype "power_in"))
      (node (ref "U9") (pin "45") (pinfunction "VDD_45") (pintype "power_in"))
      (node (ref "U9") (pin "54") (pinfunction "VCCA10SSRX12_54") (pintype "power_in"))
      (node (ref "U9") (pin "60") (pinfunction "VDD_60") (pintype "power_in"))
      (node (ref "U9") (pin "63") (pinfunction "VCCA10SSRX12_63") (pintype "power_in"))
      (node (ref "U9") (pin "9") (pinfunction "VDD_9") (pintype "power_in"))
    )
    (net (code "76") (name "VCC_3V3") (class "Default")
      (node (ref "C51") (pin "2") (pinfunction "2_2") (pintype "passive"))
      (node (ref "R58") (pin "1") (pinfunction "1_1") (pintype "passive"))
      (node (ref "U9") (pin "32") (pinfunction "VSUS33_32") (pintype "power_in"))
      (node (ref "U9") (pin "46") (pinfunction "VSUS33_46") (pintype "power_in"))
    )
    (net (code "77") (name "VCC_3V3_USB3") (class "Default")
      (node (ref "C52") (pin "2") (pinfunction "2_2") (pintype "passive"))
      (node (ref "C53") (pin "2") (pinfunction "2_2") (pintype "passive"))
      (node (ref "C70") (pin "2") (pinfunction "2_2") (pintype "passive"))
      (node (ref "C71") (pin "2") (pinfunction "2_2") (pintype "passive"))
      (node (ref "C72") (pin "2") (pinfunction "2_2") (pintype "passive"))
      (node (ref "C73") (pin "2") (pinfunction "2_2") (pintype "passive"))
      (node (ref "R58") (pin "2") (pinfunction "2_2") (pintype "passive"))
      (node (ref "R66") (pin "2") (pinfunction "2_2") (pintype "passive"))
      (node (ref "R67") (pin "2") (pinfunction "2_2") (pintype "passive"))
      (node (ref "R68") (pin "2") (pinfunction "2_2") (pintype "passive"))
      (node (ref "R71") (pin "1") (pinfunction "1_1") (pintype "passive"))
      (node (ref "R92") (pin "1") (pinfunction "1_1") (pintype "passive"))
      (node (ref "R96") (pin "1") (pinfunction "1_1") (pintype "passive"))
      (node (ref "R98") (pin "1") (pinfunction "1_1") (pintype "passive"))
      (node (ref "R99") (pin "1") (pinfunction "1_1") (pintype "passive"))
      (node (ref "U10") (pin "15") (pinfunction "VCC1_15") (pintype "power_in"))
      (node (ref "U10") (pin "29") (pinfunction "VCCOB1_29") (pintype "power_in"))
      (node (ref "U10") (pin "32") (pinfunction "VCCOB2_32") (pintype "power_in"))
      (node (ref "U10") (pin "42") (pinfunction "VCC2_42") (pintype "power_in"))
      (node (ref "U10") (pin "45") (pinfunction "VCCOC_45") (pintype "power_in"))
      (node (ref "U10") (pin "5") (pinfunction "VCCOA1_5") (pintype "power_in"))
      (node (ref "U10") (pin "8") (pinfunction "VCCOA2_8") (pintype "power_in"))
      (node (ref "U11") (pin "7") (pinfunction "~{HOLD(IO3)}_7") (pintype "bidirectional"))
      (node (ref "U11") (pin "8") (pinfunction "VCC_8") (pintype "power_in"))
      (node (ref "U9") (pin "15") (pinfunction "VCCA33SS34_15") (pintype "power_in"))
      (node (ref "U9") (pin "23") (pinfunction "VCCA33PEX_23") (pintype "power_in"))
      (node (ref "U9") (pin "49") (pinfunction "VCCA33SSM_49") (pintype "power_in"))
      (node (ref "U9") (pin "57") (pinfunction "VCCA33SS12_57") (pintype "power_in"))
      (node (ref "U9") (pin "6") (pinfunction "VCCA33SS34_6") (pintype "power_in"))
      (node (ref "U9") (pin "66") (pinfunction "VCCA33SS12_66") (pintype "power_in"))
      (node (ref "Y3") (pin "4") (pinfunction "VDD_4") (pintype "passive"))
    )
    (net (code "78") (name "VCC_USB_5V_1") (class "Default")
      (node (ref "C39") (pin "1") (pinfunction "1_1") (pintype "passive"))
      (node (ref "C45") (pin "2") (pinfunction "2_2") (pintype "passive"))
      (node (ref "C46") (pin "2") (pinfunction "2_2") (pintype "passive"))
      (node (ref "J3") (pin "B1") (pinfunction "VBUS_B1") (pintype "passive"))
      (node (ref "L5") (pin "2") (pinfunction "2_2") (pintype "passive"))
      (node (ref "R60") (pin "2") (pinfunction "2_2") (pintype "passive"))
    )
    (net (code "79") (name "VCC_USB_5V_2") (class "Default")
      (node (ref "C41") (pin "1") (pinfunction "1_1") (pintype "passive"))
      (node (ref "C47") (pin "2") (pinfunction "2_2") (pintype "passive"))
      (node (ref "C48") (pin "2") (pinfunction "2_2") (pintype "passive"))
      (node (ref "J3") (pin "A1") (pinfunction "VBUS_A1") (pintype "passive"))
      (node (ref "L6") (pin "2") (pinfunction "2_2") (pintype "passive"))
      (node (ref "R61") (pin "2") (pinfunction "2_2") (pintype "passive"))
    )
    (net (code "80") (name "VIN") (class "Default")
      (node (ref "D6") (pin "1") (pinfunction "A_1") (pintype "passive"))
      (node (ref "D7") (pin "1") (pinfunction "A_1") (pintype "passive"))
    )
    (net (code "81") (name "unconnected-(J3-GND_DRAIN-PadA7)") (class "Default")
      (node (ref "J3") (pin "A7") (pinfunction "GND_DRAIN_A7") (pintype "passive"))
    )
    (net (code "82") (name "unconnected-(J3-GND_DRAIN-PadB7)") (class "Default")
      (node (ref "J3") (pin "B7") (pinfunction "GND_DRAIN_B7") (pintype "passive"))
    )
    (net (code "83") (name "unconnected-(U9A-OVERCUR1#-Pad43)") (class "Default")
      (node (ref "U9") (pin "43") (pinfunction "OVERCUR1#_43") (pintype "input"))
    )
    (net (code "84") (name "unconnected-(U9A-OVERCUR2#-Pad41)") (class "Default")
      (node (ref "U9") (pin "41") (pinfunction "OVERCUR2#_41") (pintype "input"))
    )
    (net (code "85") (name "unconnected-(U9A-OVERCUR3#-Pad39)") (class "Default")
      (node (ref "U9") (pin "39") (pinfunction "OVERCUR3#_39") (pintype "input"))
    )
    (net (code "86") (name "unconnected-(U9A-OVERCUR4#-Pad37)") (class "Default")
      (node (ref "U9") (pin "37") (pinfunction "OVERCUR4#_37") (pintype "input"))
    )
    (net (code "87") (name "unconnected-(U9A-PEXCREQ#-Pad30)") (class "Default")
      (node (ref "U9") (pin "30") (pinfunction "PEXCREQ#_30") (pintype "passive"))
    )
    (net (code "88") (name "unconnected-(U9A-POWERON1#-Pad44)") (class "Default")
      (node (ref "U9") (pin "44") (pinfunction "POWERON1#_44") (pintype "output"))
    )
    (net (code "89") (name "unconnected-(U9A-POWERON2#-Pad42)") (class "Default")
      (node (ref "U9") (pin "42") (pinfunction "POWERON2#_42") (pintype "output"))
    )
    (net (code "90") (name "unconnected-(U9A-POWERON3#-Pad40)") (class "Default")
      (node (ref "U9") (pin "40") (pinfunction "POWERON3#_40") (pintype "output"))
    )
    (net (code "91") (name "unconnected-(U9A-POWERON4#-Pad38)") (class "Default")
      (node (ref "U9") (pin "38") (pinfunction "POWERON4#_38") (pintype "output"))
    )
    (net (code "92") (name "unconnected-(U9A-USB_DN_DN3-Pad8)") (class "Default")
      (node (ref "U9") (pin "8") (pinfunction "USB_DN_DN3_8") (pintype "bidirectional"))
    )
    (net (code "93") (name "unconnected-(U9A-USB_DN_DN4-Pad17)") (class "Default")
      (node (ref "U9") (pin "17") (pinfunction "USB_DN_DN4_17") (pintype "bidirectional"))
    )
    (net (code "94") (name "unconnected-(U9A-USB_DP_DN3-Pad7)") (class "Default")
      (node (ref "U9") (pin "7") (pinfunction "USB_DP_DN3_7") (pintype "bidirectional"))
    )
    (net (code "95") (name "unconnected-(U9A-USB_DP_DN4-Pad16)") (class "Default")
      (node (ref "U9") (pin "16") (pinfunction "USB_DP_DN4_16") (pintype "bidirectional"))
    )
    (net (code "96") (name "unconnected-(U9A-USB_SSRXN_DN3-Pad5)") (class "Default")
      (node (ref "U9") (pin "5") (pinfunction "USB_SSRXN_DN3_5") (pintype "input"))
    )
    (net (code "97") (name "unconnected-(U9A-USB_SSRXN_DN4-Pad14)") (class "Default")
      (node (ref "U9") (pin "14") (pinfunction "USB_SSRXN_DN4_14") (pintype "input"))
    )
    (net (code "98") (name "unconnected-(U9A-USB_SSRXP_DN3-Pad4)") (class "Default")
      (node (ref "U9") (pin "4") (pinfunction "USB_SSRXP_DN3_4") (pintype "input"))
    )
    (net (code "99") (name "unconnected-(U9A-USB_SSRXP_DN4-Pad13)") (class "Default")
      (node (ref "U9") (pin "13") (pinfunction "USB_SSRXP_DN4_13") (pintype "input"))
    )
    (net (code "100") (name "unconnected-(U9A-USB_SSTXN_DN3-Pad2)") (class "Default")
      (node (ref "U9") (pin "2") (pinfunction "USB_SSTXN_DN3_2") (pintype "output"))
    )
    (net (code "101") (name "unconnected-(U9A-USB_SSTXN_DN4-Pad11)") (class "Default")
      (node (ref "U9") (pin "11") (pinfunction "USB_SSTXN_DN4_11") (pintype "output"))
    )
    (net (code "102") (name "unconnected-(U9A-USB_SSTXP_DN3-Pad1)") (class "Default")
      (node (ref "U9") (pin "1") (pinfunction "USB_SSTXP_DN3_1") (pintype "output"))
    )
    (net (code "103") (name "unconnected-(U9A-USB_SSTXP_DN4-Pad10)") (class "Default")
      (node (ref "U9") (pin "10") (pinfunction "USB_SSTXP_DN4_10") (pintype "output"))
    )
    (net (code "104") (name "unconnected-(U9B-RSRVD-Pad26)") (class "Default")
      (node (ref "U9") (pin "26") (pinfunction "RSRVD_26") (pintype "passive"))
    )
    (net (code "105") (name "unconnected-(U9B-TESTEN-Pad51)") (class "Default")
      (node (ref "U9") (pin "51") (pinfunction "TESTEN_51") (pintype "passive"))
    )
    (net (code "106") (name "unconnected-(U10-CLKOUTB0*-Pad35)") (class "Default")
      (node (ref "U10") (pin "35") (pinfunction "CLKOUTB0*_35") (pintype "power_in"))
    )
    (net (code "107") (name "unconnected-(U10-CLKOUTB0-Pad36)") (class "Default")
      (node (ref "U10") (pin "36") (pinfunction "CLKOUTB0_36") (pintype "power_in"))
    )
    (net (code "108") (name "unconnected-(U10-CLKOUTB1*-Pad33)") (class "Default")
      (node (ref "U10") (pin "33") (pinfunction "CLKOUTB1*_33") (pintype "power_in"))
    )
    (net (code "109") (name "unconnected-(U10-CLKOUTB1-Pad34)") (class "Default")
      (node (ref "U10") (pin "34") (pinfunction "CLKOUTB1_34") (pintype "power_in"))
    )
    (net (code "110") (name "unconnected-(U10-CLKOUTB2*-Pad30)") (class "Default")
      (node (ref "U10") (pin "30") (pinfunction "CLKOUTB2*_30") (pintype "power_in"))
    )
    (net (code "111") (name "unconnected-(U10-CLKOUTB2-Pad31)") (class "Default")
      (node (ref "U10") (pin "31") (pinfunction "CLKOUTB2_31") (pintype "power_in"))
    )
    (net (code "112") (name "unconnected-(U10-CLKOUTB3*-Pad27)") (class "Default")
      (node (ref "U10") (pin "27") (pinfunction "CLKOUTB3*_27") (pintype "power_in"))
    )
    (net (code "113") (name "unconnected-(U10-CLKOUTB3-Pad28)") (class "Default")
      (node (ref "U10") (pin "28") (pinfunction "CLKOUTB3_28") (pintype "power_in"))
    )
    (net (code "114") (name "unconnected-(U10-CLKOUTB4*-Pad25)") (class "Default")
      (node (ref "U10") (pin "25") (pinfunction "CLKOUTB4*_25") (pintype "power_in"))
    )
    (net (code "115") (name "unconnected-(U10-CLKOUTB4-Pad26)") (class "Default")
      (node (ref "U10") (pin "26") (pinfunction "CLKOUTB4_26") (pintype "power_in"))
    )
    (net (code "116") (name "unconnected-(U10-OSCOUT-Pad17)") (class "Default")
      (node (ref "U10") (pin "17") (pinfunction "OSCOUT_17") (pintype "power_in"))
    )
    (net (code "117") (name "unconnected-(U10-REFOUT-Pad44)") (class "Default")
      (node (ref "U10") (pin "44") (pinfunction "REFOUT_44") (pintype "power_in"))
    )
    (net (code "118") (name "unconnected-(Y3-EN-Pad1)") (class "Default")
      (node (ref "Y3") (pin "1") (pinfunction "EN_1") (pintype "passive"))
    )
  )
)
